# ADC_Subsystem.net
KiCad netlist of a schematic drawn in Altium Designer
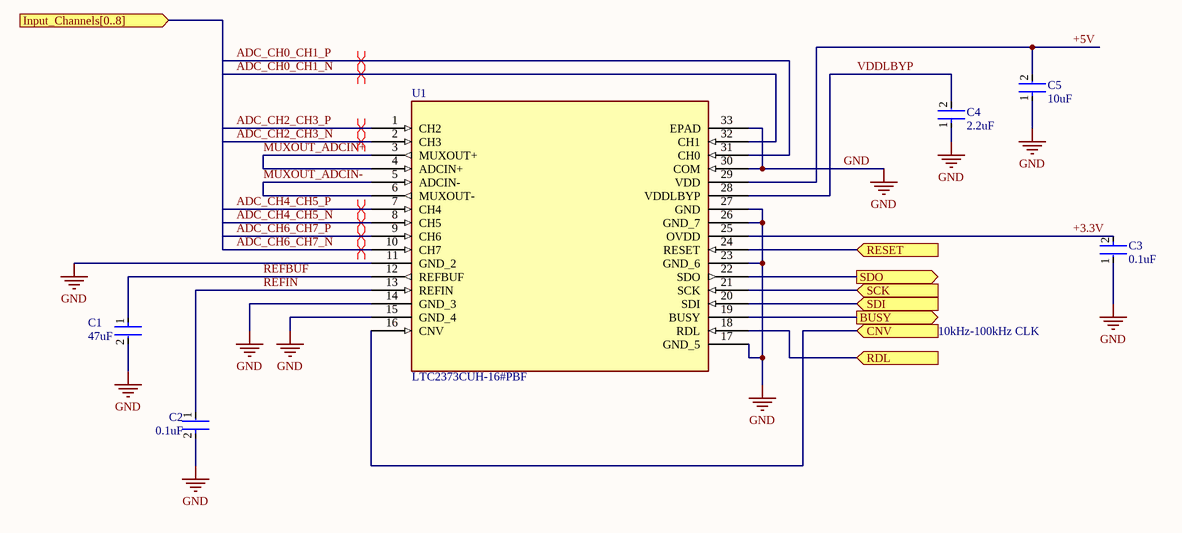
[diagram p0: ADC_Subsystem.SchDoc]

(export (version "E")
  (design (tool "Eeschema 10.0.6"))
  (components
    (comp (ref "C1")
      (value "47uF")
      (footprint "FP-C0805C476M9PACTU-MFG")
      (description "CAP CER 47UF 6.3V X5R 0805\r\nC0805C476M9PACTU")
      (fields (field (name "VOLTAGE") "6.3V") (field (name "TOLERANCE") "20%"))
      (libsource (lib "Altium Content Vault") (part "11868f565c42a9108669ba33697ecf6"))
    )
    (comp (ref "C2")
      (value "0.1uF")
      (footprint "FP-GRM15-MFG")
      (description "CAP CER 0.1UF 16V X7R 0402\r\nGRM155R71C104KA88D")
      (fields (field (name "MANUFACTURER PART NUMBER") "GRM155R71C104KA88D") (field (name "TOLERANCE") "10%"))
      (libsource (lib "Altium Content Vault") (part "236180d848d6139a670b325ea6854c9"))
    )
    (comp (ref "C3")
      (value "0.1uF")
      (footprint "FP-GRM15-MFG")
      (description "CAP CER 0.1UF 16V X7R 0402\r\nGRM155R71C104KA88D")
      (fields (field (name "MANUFACTURER PART NUMBER") "GRM155R71C104KA88D") (field (name "TOLERANCE") "10%"))
      (libsource (lib "Altium Content Vault") (part "236180d848d6139a670b325ea6854c9"))
    )
    (comp (ref "C4")
      (value "2.2uF")
      (footprint "FP-GRM188-0_1-e0_2_0_5-MFG")
      (fields (field (name "VOLTAGE") "10V") (field (name "TOLERANCE") "10%"))
      (libsource (lib "Altium Content Vault") (part "11868f565c42a9108669ba33697ecf6"))
    )
    (comp (ref "C5")
      (value "10uF")
      (footprint "FP-GRM188-0_1-e0_2_0_55-IPC_A")
      (fields (field (name "VOLTAGE") "6.3V") (field (name "TOLERANCE") "20%"))
      (libsource (lib "Altium Content Vault") (part "02cd4be3c70576c341d710602a673aa"))
    )
    (comp (ref "U1")
      (value "LTC2373CUH-16#PBF")
      (footprint "LTC_2373_Footprint")
      (libsource (lib "LTC2373CUH-16#PBF") (part "LTC2373CUH-16#PBF"))
    )
  )
  (nets
    (net (code "10") (name "/+3.3V") (class "Default")
      (node (ref "C3") (pin "2") (pinfunction "2_2") (pintype "passive"))
      (node (ref "U1") (pin "25") (pinfunction "OVDD_25") (pintype "power_in"))
    )
    (net (code "11") (name "/+5V") (class "Default")
      (node (ref "C5") (pin "2") (pinfunction "2_2") (pintype "passive"))
      (node (ref "U1") (pin "29") (pinfunction "VDD_29") (pintype "power_in"))
    )
    (net (code "12") (name "/ADC_CH0_CH1_N") (class "Default")
      (node (ref "U1") (pin "32") (pinfunction "CH1_32") (pintype "input"))
    )
    (net (code "13") (name "/ADC_CH0_CH1_P") (class "Default")
      (node (ref "U1") (pin "31") (pinfunction "CH0_31") (pintype "input"))
    )
    (net (code "14") (name "/ADC_CH2_CH3_N") (class "Default")
      (node (ref "U1") (pin "2") (pinfunction "CH3_2") (pintype "input"))
    )
    (net (code "15") (name "/ADC_CH2_CH3_P") (class "Default")
      (node (ref "U1") (pin "1") (pinfunction "CH2_1") (pintype "input"))
    )
    (net (code "16") (name "/ADC_CH4_CH5_N") (class "Default")
      (node (ref "U1") (pin "8") (pinfunction "CH5_8") (pintype "input"))
    )
    (net (code "17") (name "/ADC_CH4_CH5_P") (class "Default")
      (node (ref "U1") (pin "7") (pinfunction "CH4_7") (pintype "input"))
    )
    (net (code "18") (name "/ADC_CH6_CH7_N") (class "Default")
      (node (ref "U1") (pin "10") (pinfunction "CH7_10") (pintype "input"))
    )
    (net (code "19") (name "/ADC_CH6_CH7_P") (class "Default")
      (node (ref "U1") (pin "9") (pinfunction "CH6_9") (pintype "input"))
    )
    (net (code "20") (name "/BUSY") (class "Default")
      (node (ref "U1") (pin "19") (pinfunction "BUSY_19") (pintype "passive"))
    )
    (net (code "21") (name "/CNV") (class "Default")
      (node (ref "U1") (pin "16") (pinfunction "CNV_16") (pintype "input"))
    )
    (net (code "23") (name "/MUXOUT_ADCIN+") (class "Default")
      (node (ref "U1") (pin "3") (pinfunction "MUXOUT+_3") (pintype "output"))
      (node (ref "U1") (pin "4") (pinfunction "ADCIN+_4") (pintype "input"))
    )
    (net (code "24") (name "/MUXOUT_ADCIN-") (class "Default")
      (node (ref "U1") (pin "5") (pinfunction "ADCIN-_5") (pintype "input"))
      (node (ref "U1") (pin "6") (pinfunction "MUXOUT-_6") (pintype "output"))
    )
    (net (code "25") (name "/RDL") (class "Default")
      (node (ref "U1") (pin "18") (pinfunction "RDL_18") (pintype "input"))
    )
    (net (code "26") (name "/REFBUF") (class "Default")
      (node (ref "C1") (pin "1") (pinfunction "1_1") (pintype "passive"))
      (node (ref "U1") (pin "12") (pinfunction "REFBUF_12") (pintype "output"))
    )
    (net (code "27") (name "/REFIN") (class "Default")
      (node (ref "C2") (pin "1") (pinfunction "1_1") (pintype "passive"))
      (node (ref "U1") (pin "13") (pinfunction "REFIN_13") (pintype "input"))
    )
    (net (code "28") (name "/RESET") (class "Default")
      (node (ref "U1") (pin "24") (pinfunction "RESET_24") (pintype "input"))
    )
    (net (code "29") (name "/SCK") (class "Default")
      (node (ref "U1") (pin "21") (pinfunction "SCK_21") (pintype "input"))
    )
    (net (code "30") (name "/SDI") (class "Default")
      (node (ref "U1") (pin "20") (pinfunction "SDI_20") (pintype "input"))
    )
    (net (code "31") (name "/SDO") (class "Default")
      (node (ref "U1") (pin "22") (pinfunction "SDO_22") (pintype "output"))
    )
    (net (code "32") (name "/VDDLBYP") (class "Default")
      (node (ref "C4") (pin "2") (pinfunction "2_2") (pintype "passive"))
      (node (ref "U1") (pin "28") (pinfunction "VDDLBYP_28") (pintype "power_in"))
    )
    (net (code "33") (name "GND") (class "Default")
      (node (ref "C1") (pin "2") (pinfunction "2_2") (pintype "passive"))
      (node (ref "C2") (pin "2") (pinfunction "2_2") (pintype "passive"))
      (node (ref "C3") (pin "1") (pinfunction "1_1") (pintype "passive"))
      (node (ref "C4") (pin "1") (pinfunction "1_1") (pintype "passive"))
      (node (ref "C5") (pin "1") (pinfunction "1_1") (pintype "passive"))
      (node (ref "U1") (pin "11") (pinfunction "GND_2_11") (pintype "power_in"))
      (node (ref "U1") (pin "14") (pinfunction "GND_3_14") (pintype "power_in"))
      (node (ref "U1") (pin "15") (pinfunction "GND_4_15") (pintype "power_in"))
      (node (ref "U1") (pin "17") (pinfunction "GND_5_17") (pintype "power_in"))
      (node (ref "U1") (pin "23") (pinfunction "GND_6_23") (pintype "power_in"))
      (node (ref "U1") (pin "26") (pinfunction "GND_7_26") (pintype "power_in"))
      (node (ref "U1") (pin "27") (pinfunction "GND_27") (pintype "power_in"))
      (node (ref "U1") (pin "30") (pinfunction "COM_30") (pintype "input"))
      (node (ref "U1") (pin "33") (pinfunction "EPAD_33") (pintype "passive"))
    )
  )
)
